# AB-AudioMatrix-6x6.net
KiCad netlist of a schematic drawn in EAGLE
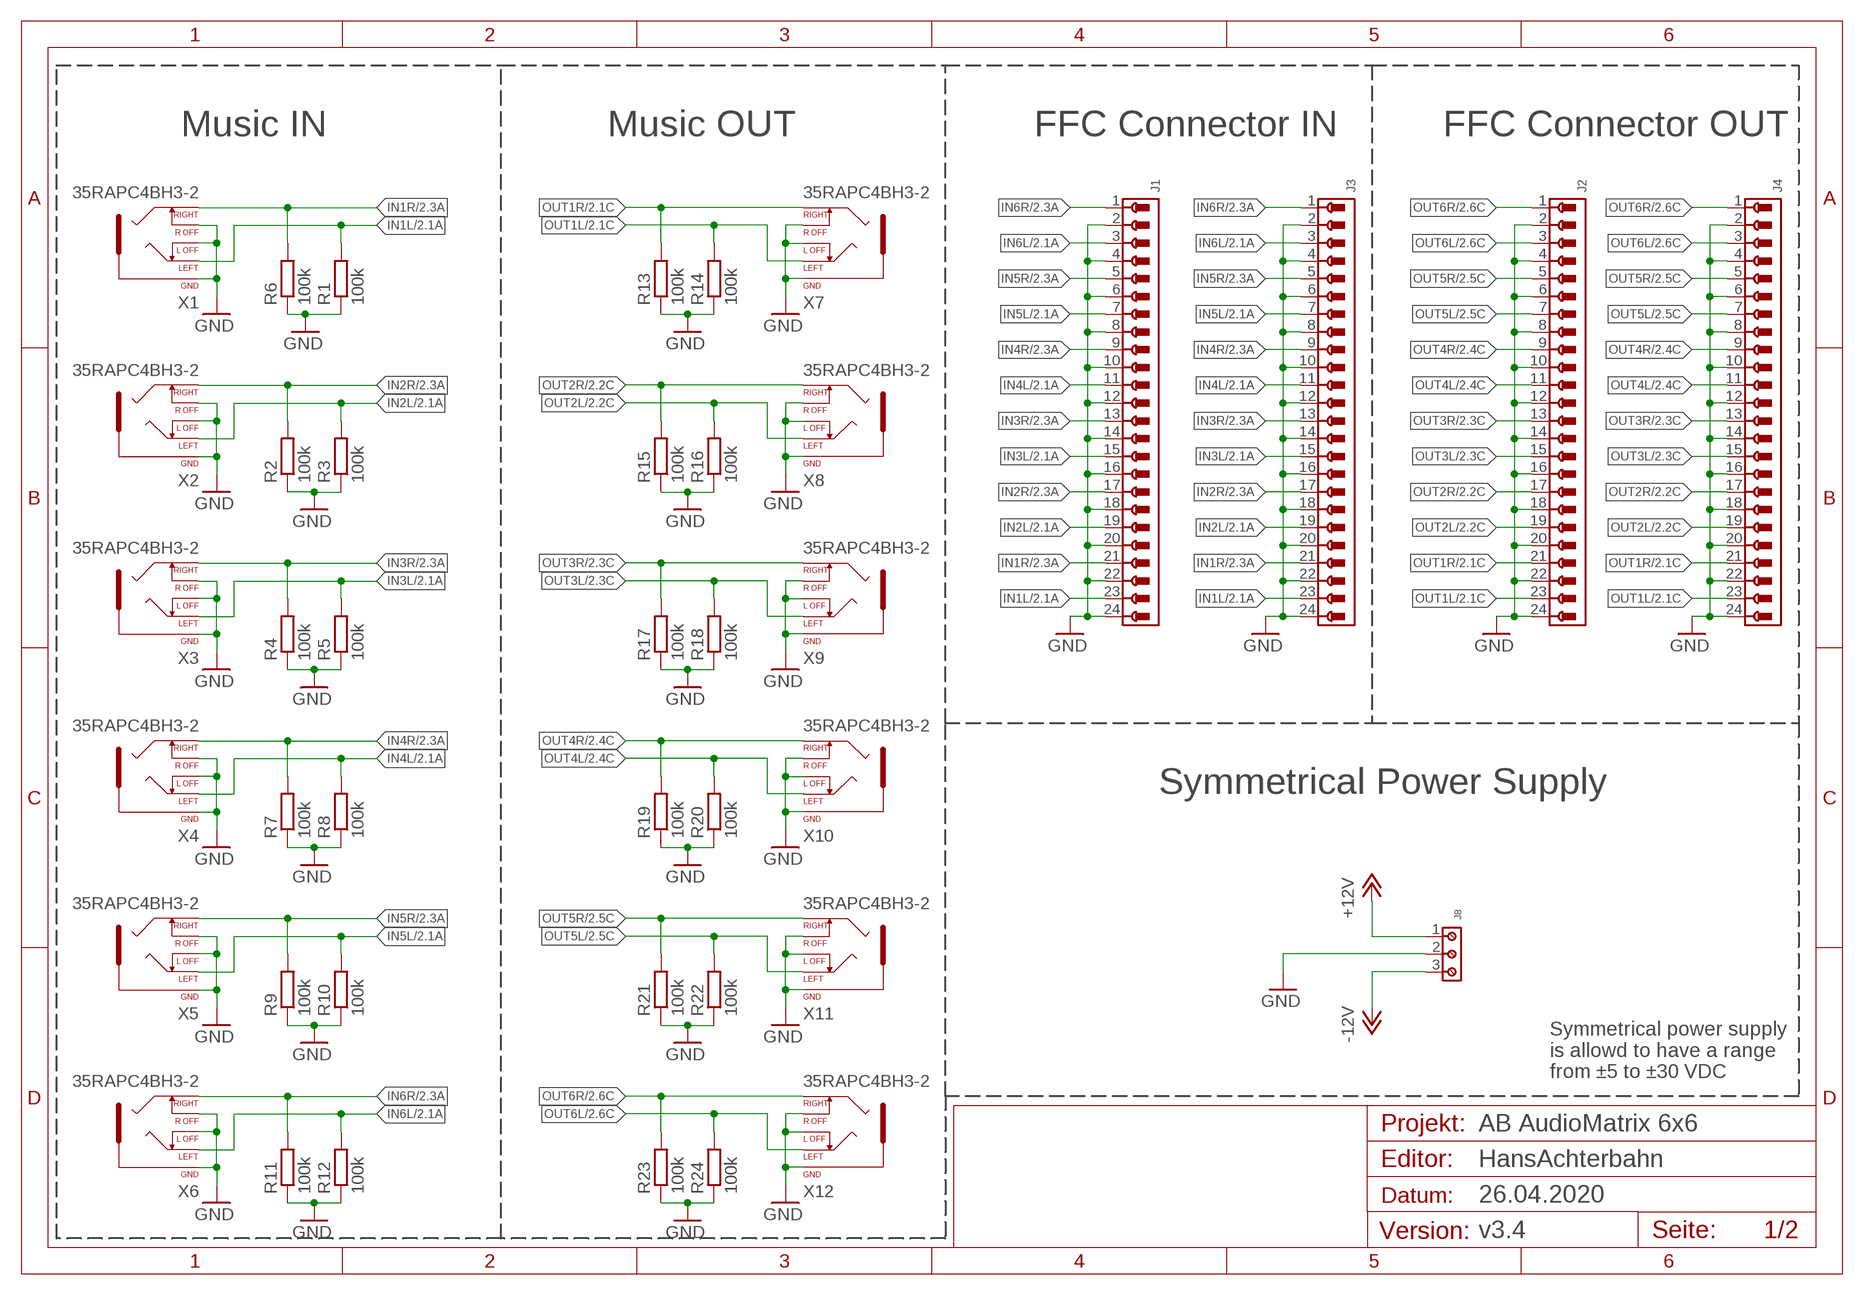
[diagram p0: schematic, sheet 1]
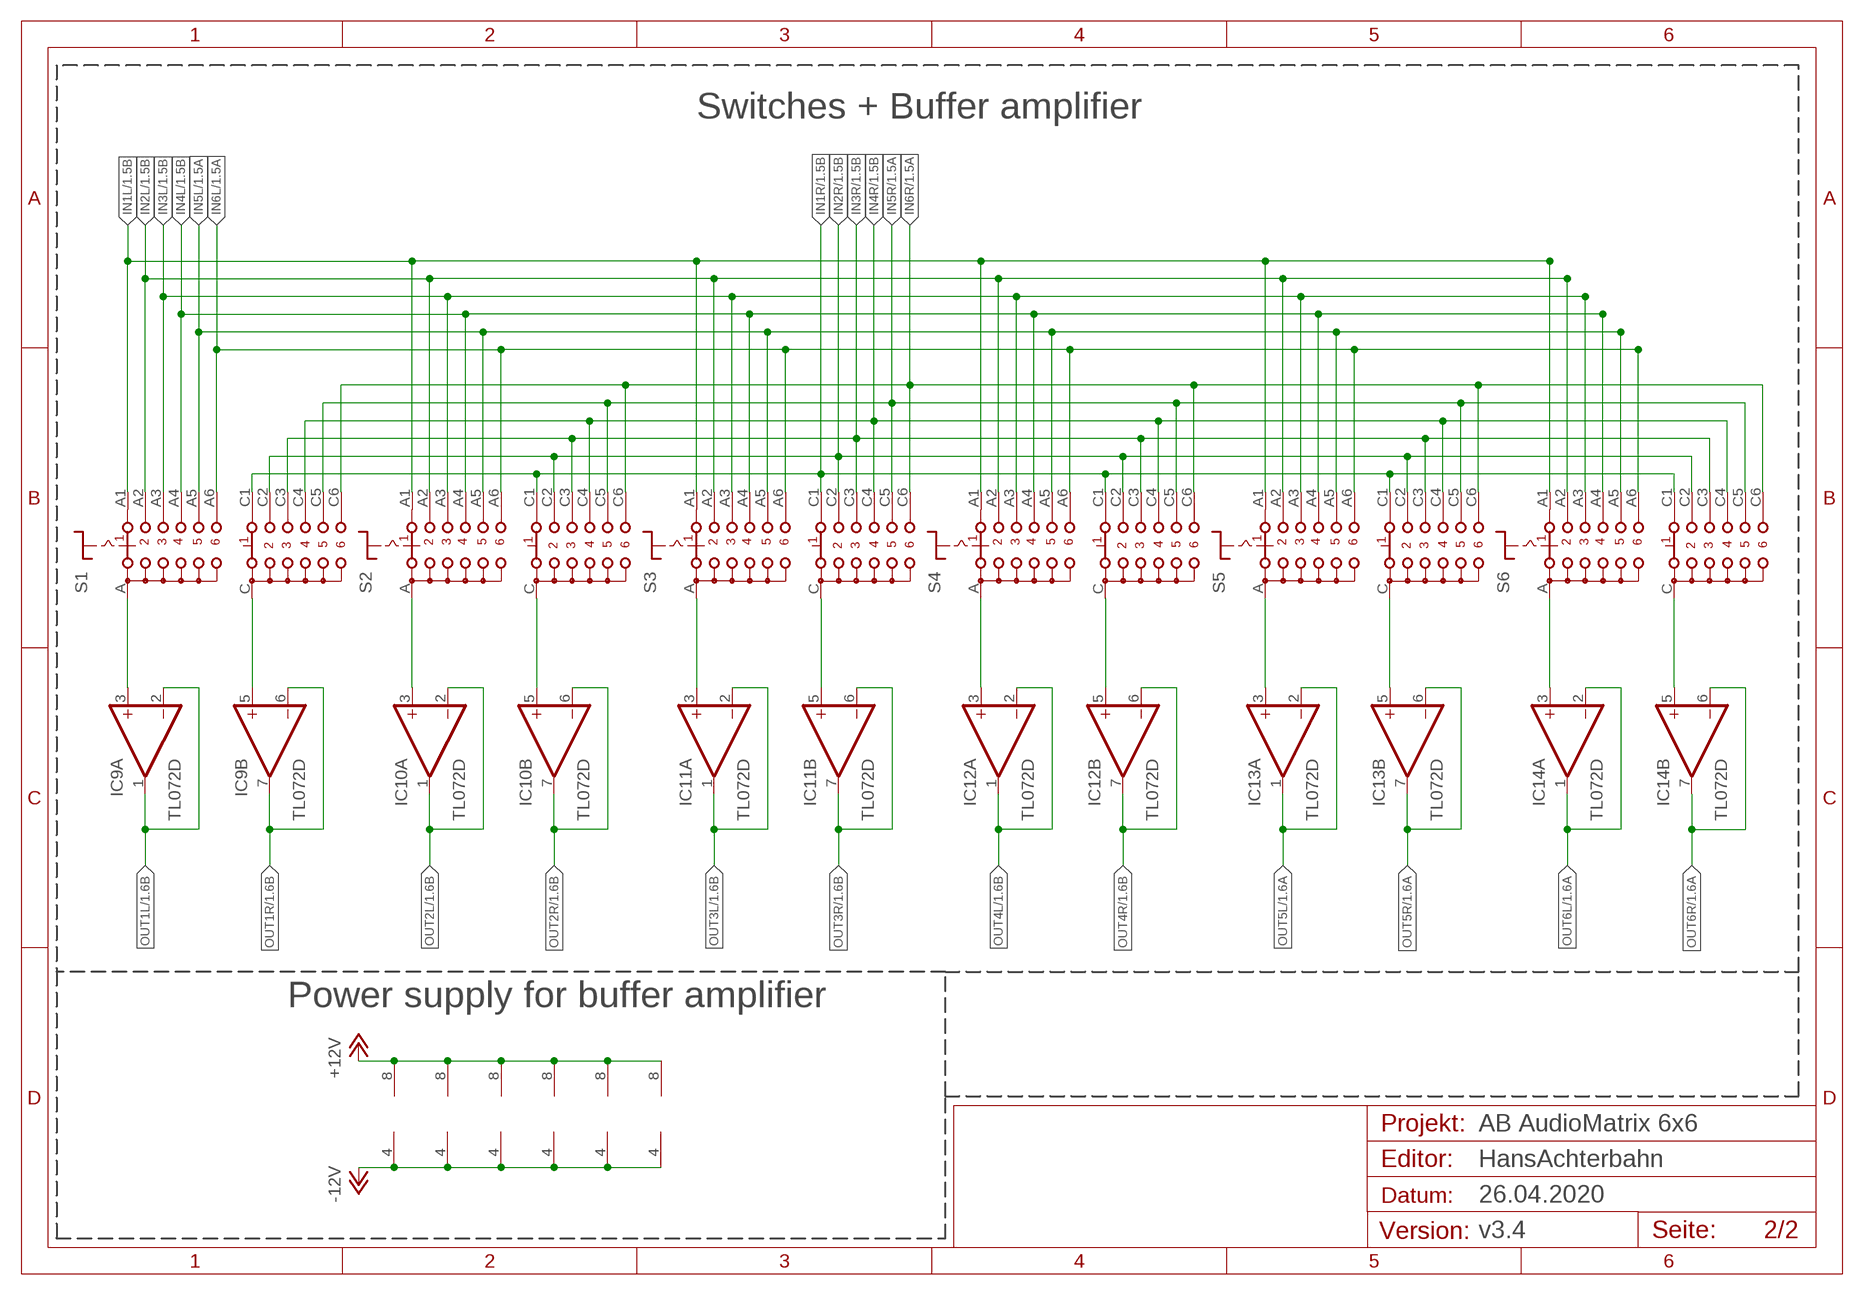
[diagram p1: schematic, sheet 2]

(export (version "E")
  (design (tool "Eeschema 10.0.6"))
  (components
    (comp (ref "J1")
      (value "6861XX188622_686124188622")
      (footprint "eagle-import:686124188622")
      (libsource (lib "eagle-import") (part "6861XX188622_686124188622"))
    )
    (comp (ref "J2")
      (value "6861XX188622_686124188622")
      (footprint "eagle-import:686124188622")
      (libsource (lib "eagle-import") (part "6861XX188622_686124188622"))
    )
    (comp (ref "J3")
      (value "6861XX188622_686124188622")
      (footprint "eagle-import:686124188622")
      (libsource (lib "eagle-import") (part "6861XX188622_686124188622"))
    )
    (comp (ref "J4")
      (value "6861XX188622_686124188622")
      (footprint "eagle-import:686124188622")
      (libsource (lib "eagle-import") (part "6861XX188622_686124188622"))
    )
    (comp (ref "J8")
      (value "691102710003")
      (footprint "eagle-import:691102710003")
      (libsource (lib "eagle-import") (part "691102710003"))
    )
    (comp (ref "R1")
      (value "100k")
      (footprint "eagle-import:R0603")
      (fields (field (name "MF") "Vishay"))
      (libsource (lib "eagle-import") (part "R-EU_R0603"))
    )
    (comp (ref "R2")
      (value "100k")
      (footprint "eagle-import:R0603")
      (fields (field (name "MF") "Vishay"))
      (libsource (lib "eagle-import") (part "R-EU_R0603"))
    )
    (comp (ref "R3")
      (value "100k")
      (footprint "eagle-import:R0603")
      (fields (field (name "MF") "Vishay"))
      (libsource (lib "eagle-import") (part "R-EU_R0603"))
    )
    (comp (ref "R4")
      (value "100k")
      (footprint "eagle-import:R0603")
      (fields (field (name "MF") "Vishay"))
      (libsource (lib "eagle-import") (part "R-EU_R0603"))
    )
    (comp (ref "R5")
      (value "100k")
      (footprint "eagle-import:R0603")
      (fields (field (name "MF") "Vishay"))
      (libsource (lib "eagle-import") (part "R-EU_R0603"))
    )
    (comp (ref "R6")
      (value "100k")
      (footprint "eagle-import:R0603")
      (fields (field (name "MF") "Vishay"))
      (libsource (lib "eagle-import") (part "R-EU_R0603"))
    )
    (comp (ref "R7")
      (value "100k")
      (footprint "eagle-import:R0603")
      (fields (field (name "MF") "Vishay"))
      (libsource (lib "eagle-import") (part "R-EU_R0603"))
    )
    (comp (ref "R8")
      (value "100k")
      (footprint "eagle-import:R0603")
      (fields (field (name "MF") "Vishay"))
      (libsource (lib "eagle-import") (part "R-EU_R0603"))
    )
    (comp (ref "R9")
      (value "100k")
      (footprint "eagle-import:R0603")
      (fields (field (name "MF") "Vishay"))
      (libsource (lib "eagle-import") (part "R-EU_R0603"))
    )
    (comp (ref "R10")
      (value "100k")
      (footprint "eagle-import:R0603")
      (fields (field (name "MF") "Vishay"))
      (libsource (lib "eagle-import") (part "R-EU_R0603"))
    )
    (comp (ref "R11")
      (value "100k")
      (footprint "eagle-import:R0603")
      (fields (field (name "MF") "Vishay"))
      (libsource (lib "eagle-import") (part "R-EU_R0603"))
    )
    (comp (ref "R12")
      (value "100k")
      (footprint "eagle-import:R0603")
      (fields (field (name "MF") "Vishay"))
      (libsource (lib "eagle-import") (part "R-EU_R0603"))
    )
    (comp (ref "R13")
      (value "100k")
      (footprint "eagle-import:R0603")
      (fields (field (name "MF") "Vishay"))
      (libsource (lib "eagle-import") (part "R-EU_R0603"))
    )
    (comp (ref "R14")
      (value "100k")
      (footprint "eagle-import:R0603")
      (fields (field (name "MF") "Vishay"))
      (libsource (lib "eagle-import") (part "R-EU_R0603"))
    )
    (comp (ref "R15")
      (value "100k")
      (footprint "eagle-import:R0603")
      (fields (field (name "MF") "Vishay"))
      (libsource (lib "eagle-import") (part "R-EU_R0603"))
    )
    (comp (ref "R16")
      (value "100k")
      (footprint "eagle-import:R0603")
      (fields (field (name "MF") "Vishay"))
      (libsource (lib "eagle-import") (part "R-EU_R0603"))
    )
    (comp (ref "R17")
      (value "100k")
      (footprint "eagle-import:R0603")
      (fields (field (name "MF") "Vishay"))
      (libsource (lib "eagle-import") (part "R-EU_R0603"))
    )
    (comp (ref "R18")
      (value "100k")
      (footprint "eagle-import:R0603")
      (fields (field (name "MF") "Vishay"))
      (libsource (lib "eagle-import") (part "R-EU_R0603"))
    )
    (comp (ref "R19")
      (value "100k")
      (footprint "eagle-import:R0603")
      (fields (field (name "MF") "Vishay"))
      (libsource (lib "eagle-import") (part "R-EU_R0603"))
    )
    (comp (ref "R20")
      (value "100k")
      (footprint "eagle-import:R0603")
      (fields (field (name "MF") "Vishay"))
      (libsource (lib "eagle-import") (part "R-EU_R0603"))
    )
    (comp (ref "R21")
      (value "100k")
      (footprint "eagle-import:R0603")
      (fields (field (name "MF") "Vishay"))
      (libsource (lib "eagle-import") (part "R-EU_R0603"))
    )
    (comp (ref "R22")
      (value "100k")
      (footprint "eagle-import:R0603")
      (fields (field (name "MF") "Vishay"))
      (libsource (lib "eagle-import") (part "R-EU_R0603"))
    )
    (comp (ref "R23")
      (value "100k")
      (footprint "eagle-import:R0603")
      (fields (field (name "MF") "Vishay"))
      (libsource (lib "eagle-import") (part "R-EU_R0603"))
    )
    (comp (ref "R24")
      (value "100k")
      (footprint "eagle-import:R0603")
      (fields (field (name "MF") "Vishay"))
      (libsource (lib "eagle-import") (part "R-EU_R0603"))
    )
    (comp (ref "X1")
      (value "35RAPC4BH3-2")
      (footprint "eagle-import:SWITCHCRAFT_35RAPC4BH3")
      (fields
        (field (name "MF") "Switchcraft")
        (field (name "MF_1") "Switchcraft")
        (field (name "MFN") "35RAPC4BH3")
        (field (name "MOUSER") "502-35RAPC4BH3")
        (field (name "RS-ONLINE") "878-7229")
      )
      (libsource (lib "eagle-import") (part "35RAPC4BH3-2"))
    )
    (comp (ref "X2")
      (value "35RAPC4BH3-2")
      (footprint "eagle-import:SWITCHCRAFT_35RAPC4BH3")
      (fields (field (name "MF") "Switchcraft"))
      (libsource (lib "eagle-import") (part "35RAPC4BH3-2"))
    )
    (comp (ref "X3")
      (value "35RAPC4BH3-2")
      (footprint "eagle-import:SWITCHCRAFT_35RAPC4BH3")
      (fields (field (name "MF") "Switchcraft"))
      (libsource (lib "eagle-import") (part "35RAPC4BH3-2"))
    )
    (comp (ref "X4")
      (value "35RAPC4BH3-2")
      (footprint "eagle-import:SWITCHCRAFT_35RAPC4BH3")
      (fields (field (name "MF") "Switchcraft"))
      (libsource (lib "eagle-import") (part "35RAPC4BH3-2"))
    )
    (comp (ref "X5")
      (value "35RAPC4BH3-2")
      (footprint "eagle-import:SWITCHCRAFT_35RAPC4BH3")
      (fields (field (name "MF") "Switchcraft"))
      (libsource (lib "eagle-import") (part "35RAPC4BH3-2"))
    )
    (comp (ref "X6")
      (value "35RAPC4BH3-2")
      (footprint "eagle-import:SWITCHCRAFT_35RAPC4BH3")
      (fields (field (name "MF") "Switchcraft"))
      (libsource (lib "eagle-import") (part "35RAPC4BH3-2"))
    )
    (comp (ref "X7")
      (value "35RAPC4BH3-2")
      (footprint "eagle-import:SWITCHCRAFT_35RAPC4BH3")
      (fields (field (name "MF") "Switchcraft"))
      (libsource (lib "eagle-import") (part "35RAPC4BH3-2"))
    )
    (comp (ref "X8")
      (value "35RAPC4BH3-2")
      (footprint "eagle-import:SWITCHCRAFT_35RAPC4BH3")
      (fields (field (name "MF") "Switchcraft"))
      (libsource (lib "eagle-import") (part "35RAPC4BH3-2"))
    )
    (comp (ref "X9")
      (value "35RAPC4BH3-2")
      (footprint "eagle-import:SWITCHCRAFT_35RAPC4BH3")
      (fields (field (name "MF") "Switchcraft"))
      (libsource (lib "eagle-import") (part "35RAPC4BH3-2"))
    )
    (comp (ref "X10")
      (value "35RAPC4BH3-2")
      (footprint "eagle-import:SWITCHCRAFT_35RAPC4BH3")
      (fields (field (name "MF") "Switchcraft"))
      (libsource (lib "eagle-import") (part "35RAPC4BH3-2"))
    )
    (comp (ref "X11")
      (value "35RAPC4BH3-2")
      (footprint "eagle-import:SWITCHCRAFT_35RAPC4BH3")
      (fields (field (name "MF") "Switchcraft"))
      (libsource (lib "eagle-import") (part "35RAPC4BH3-2"))
    )
    (comp (ref "X12")
      (value "35RAPC4BH3-2")
      (footprint "eagle-import:SWITCHCRAFT_35RAPC4BH3")
      (fields (field (name "MF") "Switchcraft"))
      (libsource (lib "eagle-import") (part "35RAPC4BH3-2"))
    )
    (comp (ref "IC9")
      (value "TL072D")
      (footprint "eagle-import:SO08")
      (libsource (lib "eagle-import") (part "TL072D"))
    )
    (comp (ref "IC10")
      (value "TL072D")
      (footprint "eagle-import:SO08")
      (libsource (lib "eagle-import") (part "TL072D"))
    )
    (comp (ref "IC11")
      (value "TL072D")
      (footprint "eagle-import:SO08")
      (libsource (lib "eagle-import") (part "TL072D"))
    )
    (comp (ref "IC12")
      (value "TL072D")
      (footprint "eagle-import:SO08")
      (libsource (lib "eagle-import") (part "TL072D"))
    )
    (comp (ref "IC13")
      (value "TL072D")
      (footprint "eagle-import:SO08")
      (libsource (lib "eagle-import") (part "TL072D"))
    )
    (comp (ref "IC14")
      (value "TL072D")
      (footprint "eagle-import:SO08")
      (libsource (lib "eagle-import") (part "TL072D"))
    )
    (comp (ref "S1")
      (value "CK102X06")
      (footprint "eagle-import:CK102X06")
      (fields (field (name "MF") "Lorlin"))
      (libsource (lib "eagle-import") (part "CK102X06"))
    )
    (comp (ref "S2")
      (value "CK102X06")
      (footprint "eagle-import:CK102X06")
      (fields (field (name "MF") "Lorlin"))
      (libsource (lib "eagle-import") (part "CK102X06"))
    )
    (comp (ref "S3")
      (value "CK102X06")
      (footprint "eagle-import:CK102X06")
      (fields (field (name "MF") "Lorlin"))
      (libsource (lib "eagle-import") (part "CK102X06"))
    )
    (comp (ref "S4")
      (value "CK102X06")
      (footprint "eagle-import:CK102X06")
      (fields (field (name "MF") "Lorlin"))
      (libsource (lib "eagle-import") (part "CK102X06"))
    )
    (comp (ref "S5")
      (value "CK102X06")
      (footprint "eagle-import:CK102X06")
      (fields (field (name "MF") "Lorlin"))
      (libsource (lib "eagle-import") (part "CK102X06"))
    )
    (comp (ref "S6")
      (value "CK102X06")
      (footprint "eagle-import:CK102X06")
      (fields (field (name "MF") "Lorlin"))
      (libsource (lib "eagle-import") (part "CK102X06"))
    )
  )
  (nets
    (net (code "1") (name "+12V") (class "Default")
      (node (ref "IC10") (pin "8") (pinfunction "V+_8") (pintype "power_in"))
      (node (ref "IC11") (pin "8") (pinfunction "V+_8") (pintype "power_in"))
      (node (ref "IC12") (pin "8") (pinfunction "V+_8") (pintype "power_in"))
      (node (ref "IC13") (pin "8") (pinfunction "V+_8") (pintype "power_in"))
      (node (ref "IC14") (pin "8") (pinfunction "V+_8") (pintype "power_in"))
      (node (ref "IC9") (pin "8") (pinfunction "V+_8") (pintype "power_in"))
      (node (ref "J8") (pin "1") (pinfunction "1_1") (pintype "passive"))
    )
    (net (code "2") (name "-12V") (class "Default")
      (node (ref "IC10") (pin "4") (pinfunction "V-_4") (pintype "power_in"))
      (node (ref "IC11") (pin "4") (pinfunction "V-_4") (pintype "power_in"))
      (node (ref "IC12") (pin "4") (pinfunction "V-_4") (pintype "power_in"))
      (node (ref "IC13") (pin "4") (pinfunction "V-_4") (pintype "power_in"))
      (node (ref "IC14") (pin "4") (pinfunction "V-_4") (pintype "power_in"))
      (node (ref "IC9") (pin "4") (pinfunction "V-_4") (pintype "power_in"))
      (node (ref "J8") (pin "3") (pinfunction "3_3") (pintype "passive"))
    )
    (net (code "3") (name "GND") (class "Default")
      (node (ref "J1") (pin "10") (pinfunction "10_10") (pintype "passive"))
      (node (ref "J1") (pin "12") (pinfunction "12_12") (pintype "passive"))
      (node (ref "J1") (pin "14") (pinfunction "14_14") (pintype "passive"))
      (node (ref "J1") (pin "16") (pinfunction "16_16") (pintype "passive"))
      (node (ref "J1") (pin "18") (pinfunction "18_18") (pintype "passive"))
      (node (ref "J1") (pin "2") (pinfunction "2_2") (pintype "passive"))
      (node (ref "J1") (pin "20") (pinfunction "20_20") (pintype "passive"))
      (node (ref "J1") (pin "22") (pinfunction "22_22") (pintype "passive"))
      (node (ref "J1") (pin "24") (pinfunction "24_24") (pintype "passive"))
      (node (ref "J1") (pin "4") (pinfunction "4_4") (pintype "passive"))
      (node (ref "J1") (pin "6") (pinfunction "6_6") (pintype "passive"))
      (node (ref "J1") (pin "8") (pinfunction "8_8") (pintype "passive"))
      (node (ref "J2") (pin "10") (pinfunction "10_10") (pintype "passive"))
      (node (ref "J2") (pin "12") (pinfunction "12_12") (pintype "passive"))
      (node (ref "J2") (pin "14") (pinfunction "14_14") (pintype "passive"))
      (node (ref "J2") (pin "16") (pinfunction "16_16") (pintype "passive"))
      (node (ref "J2") (pin "18") (pinfunction "18_18") (pintype "passive"))
      (node (ref "J2") (pin "2") (pinfunction "2_2") (pintype "passive"))
      (node (ref "J2") (pin "20") (pinfunction "20_20") (pintype "passive"))
      (node (ref "J2") (pin "22") (pinfunction "22_22") (pintype "passive"))
      (node (ref "J2") (pin "24") (pinfunction "24_24") (pintype "passive"))
      (node (ref "J2") (pin "4") (pinfunction "4_4") (pintype "passive"))
      (node (ref "J2") (pin "6") (pinfunction "6_6") (pintype "passive"))
      (node (ref "J2") (pin "8") (pinfunction "8_8") (pintype "passive"))
      (node (ref "J3") (pin "10") (pinfunction "10_10") (pintype "passive"))
      (node (ref "J3") (pin "12") (pinfunction "12_12") (pintype "passive"))
      (node (ref "J3") (pin "14") (pinfunction "14_14") (pintype "passive"))
      (node (ref "J3") (pin "16") (pinfunction "16_16") (pintype "passive"))
      (node (ref "J3") (pin "18") (pinfunction "18_18") (pintype "passive"))
      (node (ref "J3") (pin "2") (pinfunction "2_2") (pintype "passive"))
      (node (ref "J3") (pin "20") (pinfunction "20_20") (pintype "passive"))
      (node (ref "J3") (pin "22") (pinfunction "22_22") (pintype "passive"))
      (node (ref "J3") (pin "24") (pinfunction "24_24") (pintype "passive"))
      (node (ref "J3") (pin "4") (pinfunction "4_4") (pintype "passive"))
      (node (ref "J3") (pin "6") (pinfunction "6_6") (pintype "passive"))
      (node (ref "J3") (pin "8") (pinfunction "8_8") (pintype "passive"))
      (node (ref "J4") (pin "10") (pinfunction "10_10") (pintype "passive"))
      (node (ref "J4") (pin "12") (pinfunction "12_12") (pintype "passive"))
      (node (ref "J4") (pin "14") (pinfunction "14_14") (pintype "passive"))
      (node (ref "J4") (pin "16") (pinfunction "16_16") (pintype "passive"))
      (node (ref "J4") (pin "18") (pinfunction "18_18") (pintype "passive"))
      (node (ref "J4") (pin "2") (pinfunction "2_2") (pintype "passive"))
      (node (ref "J4") (pin "20") (pinfunction "20_20") (pintype "passive"))
      (node (ref "J4") (pin "22") (pinfunction "22_22") (pintype "passive"))
      (node (ref "J4") (pin "24") (pinfunction "24_24") (pintype "passive"))
      (node (ref "J4") (pin "4") (pinfunction "4_4") (pintype "passive"))
      (node (ref "J4") (pin "6") (pinfunction "6_6") (pintype "passive"))
      (node (ref "J4") (pin "8") (pinfunction "8_8") (pintype "passive"))
      (node (ref "J8") (pin "2") (pinfunction "2_2") (pintype "passive"))
      (node (ref "R1") (pin "1") (pinfunction "1_1") (pintype "passive"))
      (node (ref "R10") (pin "1") (pinfunction "1_1") (pintype "passive"))
      (node (ref "R11") (pin "1") (pinfunction "1_1") (pintype "passive"))
      (node (ref "R12") (pin "1") (pinfunction "1_1") (pintype "passive"))
      (node (ref "R13") (pin "1") (pinfunction "1_1") (pintype "passive"))
      (node (ref "R14") (pin "1") (pinfunction "1_1") (pintype "passive"))
      (node (ref "R15") (pin "1") (pinfunction "1_1") (pintype "passive"))
      (node (ref "R16") (pin "1") (pinfunction "1_1") (pintype "passive"))
      (node (ref "R17") (pin "1") (pinfunction "1_1") (pintype "passive"))
      (node (ref "R18") (pin "1") (pinfunction "1_1") (pintype "passive"))
      (node (ref "R19") (pin "1") (pinfunction "1_1") (pintype "passive"))
      (node (ref "R2") (pin "1") (pinfunction "1_1") (pintype "passive"))
      (node (ref "R20") (pin "1") (pinfunction "1_1") (pintype "passive"))
      (node (ref "R21") (pin "1") (pinfunction "1_1") (pintype "passive"))
      (node (ref "R22") (pin "1") (pinfunction "1_1") (pintype "passive"))
      (node (ref "R23") (pin "1") (pinfunction "1_1") (pintype "passive"))
      (node (ref "R24") (pin "1") (pinfunction "1_1") (pintype "passive"))
      (node (ref "R3") (pin "1") (pinfunction "1_1") (pintype "passive"))
      (node (ref "R4") (pin "1") (pinfunction "1_1") (pintype "passive"))
      (node (ref "R5") (pin "1") (pinfunction "1_1") (pintype "passive"))
      (node (ref "R6") (pin "1") (pinfunction "1_1") (pintype "passive"))
      (node (ref "R7") (pin "1") (pinfunction "1_1") (pintype "passive"))
      (node (ref "R8") (pin "1") (pinfunction "1_1") (pintype "passive"))
      (node (ref "R9") (pin "1") (pinfunction "1_1") (pintype "passive"))
      (node (ref "X1") (pin "1") (pinfunction "GND_1") (pintype "bidirectional"))
      (node (ref "X1") (pin "3") (pinfunction "RIGHT_OFF_3") (pintype "bidirectional"))
      (node (ref "X1") (pin "4") (pinfunction "LEFT_OFF_4") (pintype "bidirectional"))
      (node (ref "X10") (pin "1") (pinfunction "GND_1") (pintype "bidirectional"))
      (node (ref "X10") (pin "3") (pinfunction "RIGHT_OFF_3") (pintype "bidirectional"))
      (node (ref "X10") (pin "4") (pinfunction "LEFT_OFF_4") (pintype "bidirectional"))
      (node (ref "X11") (pin "1") (pinfunction "GND_1") (pintype "bidirectional"))
      (node (ref "X11") (pin "3") (pinfunction "RIGHT_OFF_3") (pintype "bidirectional"))
      (node (ref "X11") (pin "4") (pinfunction "LEFT_OFF_4") (pintype "bidirectional"))
      (node (ref "X12") (pin "1") (pinfunction "GND_1") (pintype "bidirectional"))
      (node (ref "X12") (pin "3") (pinfunction "RIGHT_OFF_3") (pintype "bidirectional"))
      (node (ref "X12") (pin "4") (pinfunction "LEFT_OFF_4") (pintype "bidirectional"))
      (node (ref "X2") (pin "1") (pinfunction "GND_1") (pintype "bidirectional"))
      (node (ref "X2") (pin "3") (pinfunction "RIGHT_OFF_3") (pintype "bidirectional"))
      (node (ref "X2") (pin "4") (pinfunction "LEFT_OFF_4") (pintype "bidirectional"))
      (node (ref "X3") (pin "1") (pinfunction "GND_1") (pintype "bidirectional"))
      (node (ref "X3") (pin "3") (pinfunction "RIGHT_OFF_3") (pintype "bidirectional"))
      (node (ref "X3") (pin "4") (pinfunction "LEFT_OFF_4") (pintype "bidirectional"))
      (node (ref "X4") (pin "1") (pinfunction "GND_1") (pintype "bidirectional"))
      (node (ref "X4") (pin "3") (pinfunction "RIGHT_OFF_3") (pintype "bidirectional"))
      (node (ref "X4") (pin "4") (pinfunction "LEFT_OFF_4") (pintype "bidirectional"))
      (node (ref "X5") (pin "1") (pinfunction "GND_1") (pintype "bidirectional"))
      (node (ref "X5") (pin "3") (pinfunction "RIGHT_OFF_3") (pintype "bidirectional"))
      (node (ref "X5") (pin "4") (pinfunction "LEFT_OFF_4") (pintype "bidirectional"))
      (node (ref "X6") (pin "1") (pinfunction "GND_1") (pintype "bidirectional"))
      (node (ref "X6") (pin "3") (pinfunction "RIGHT_OFF_3") (pintype "bidirectional"))
      (node (ref "X6") (pin "4") (pinfunction "LEFT_OFF_4") (pintype "bidirectional"))
      (node (ref "X7") (pin "1") (pinfunction "GND_1") (pintype "bidirectional"))
      (node (ref "X7") (pin "3") (pinfunction "RIGHT_OFF_3") (pintype "bidirectional"))
      (node (ref "X7") (pin "4") (pinfunction "LEFT_OFF_4") (pintype "bidirectional"))
      (node (ref "X8") (pin "1") (pinfunction "GND_1") (pintype "bidirectional"))
      (node (ref "X8") (pin "3") (pinfunction "RIGHT_OFF_3") (pintype "bidirectional"))
      (node (ref "X8") (pin "4") (pinfunction "LEFT_OFF_4") (pintype "bidirectional"))
      (node (ref "X9") (pin "1") (pinfunction "GND_1") (pintype "bidirectional"))
      (node (ref "X9") (pin "3") (pinfunction "RIGHT_OFF_3") (pintype "bidirectional"))
      (node (ref "X9") (pin "4") (pinfunction "LEFT_OFF_4") (pintype "bidirectional"))
    )
    (net (code "4") (name "IN1L") (class "Default")
      (node (ref "J1") (pin "23") (pinfunction "23_23") (pintype "passive"))
      (node (ref "J3") (pin "23") (pinfunction "23_23") (pintype "passive"))
      (node (ref "R1") (pin "2") (pinfunction "2_2") (pintype "passive"))
      (node (ref "S1") (pin "A1") (pinfunction "A1_A1") (pintype "passive"))
      (node (ref "S2") (pin "A1") (pinfunction "A1_A1") (pintype "passive"))
      (node (ref "S3") (pin "A1") (pinfunction "A1_A1") (pintype "passive"))
      (node (ref "S4") (pin "A1") (pinfunction "A1_A1") (pintype "passive"))
      (node (ref "S5") (pin "A1") (pinfunction "A1_A1") (pintype "passive"))
      (node (ref "S6") (pin "A1") (pinfunction "A1_A1") (pintype "passive"))
      (node (ref "X1") (pin "5") (pinfunction "LEFT_5") (pintype "bidirectional"))
    )
    (net (code "5") (name "IN1R") (class "Default")
      (node (ref "J1") (pin "21") (pinfunction "21_21") (pintype "passive"))
      (node (ref "J3") (pin "21") (pinfunction "21_21") (pintype "passive"))
      (node (ref "R6") (pin "2") (pinfunction "2_2") (pintype "passive"))
      (node (ref "S1") (pin "C1") (pinfunction "C1_C1") (pintype "passive"))
      (node (ref "S2") (pin "C1") (pinfunction "C1_C1") (pintype "passive"))
      (node (ref "S3") (pin "C1") (pinfunction "C1_C1") (pintype "passive"))
      (node (ref "S4") (pin "C1") (pinfunction "C1_C1") (pintype "passive"))
      (node (ref "S5") (pin "C1") (pinfunction "C1_C1") (pintype "passive"))
      (node (ref "S6") (pin "C1") (pinfunction "C1_C1") (pintype "passive"))
      (node (ref "X1") (pin "2") (pinfunction "RIGHT_2") (pintype "bidirectional"))
    )
    (net (code "6") (name "IN2L") (class "Default")
      (node (ref "J1") (pin "19") (pinfunction "19_19") (pintype "passive"))
      (node (ref "J3") (pin "19") (pinfunction "19_19") (pintype "passive"))
      (node (ref "R3") (pin "2") (pinfunction "2_2") (pintype "passive"))
      (node (ref "S1") (pin "A2") (pinfunction "A2_A2") (pintype "passive"))
      (node (ref "S2") (pin "A2") (pinfunction "A2_A2") (pintype "passive"))
      (node (ref "S3") (pin "A2") (pinfunction "A2_A2") (pintype "passive"))
      (node (ref "S4") (pin "A2") (pinfunction "A2_A2") (pintype "passive"))
      (node (ref "S5") (pin "A2") (pinfunction "A2_A2") (pintype "passive"))
      (node (ref "S6") (pin "A2") (pinfunction "A2_A2") (pintype "passive"))
      (node (ref "X2") (pin "5") (pinfunction "LEFT_5") (pintype "bidirectional"))
    )
    (net (code "7") (name "IN2R") (class "Default")
      (node (ref "J1") (pin "17") (pinfunction "17_17") (pintype "passive"))
      (node (ref "J3") (pin "17") (pinfunction "17_17") (pintype "passive"))
      (node (ref "R2") (pin "2") (pinfunction "2_2") (pintype "passive"))
      (node (ref "S1") (pin "C2") (pinfunction "C2_C2") (pintype "passive"))
      (node (ref "S2") (pin "C2") (pinfunction "C2_C2") (pintype "passive"))
      (node (ref "S3") (pin "C2") (pinfunction "C2_C2") (pintype "passive"))
      (node (ref "S4") (pin "C2") (pinfunction "C2_C2") (pintype "passive"))
      (node (ref "S5") (pin "C2") (pinfunction "C2_C2") (pintype "passive"))
      (node (ref "S6") (pin "C2") (pinfunction "C2_C2") (pintype "passive"))
      (node (ref "X2") (pin "2") (pinfunction "RIGHT_2") (pintype "bidirectional"))
    )
    (net (code "8") (name "IN3L") (class "Default")
      (node (ref "J1") (pin "15") (pinfunction "15_15") (pintype "passive"))
      (node (ref "J3") (pin "15") (pinfunction "15_15") (pintype "passive"))
      (node (ref "R5") (pin "2") (pinfunction "2_2") (pintype "passive"))
      (node (ref "S1") (pin "A3") (pinfunction "A3_A3") (pintype "passive"))
      (node (ref "S2") (pin "A3") (pinfunction "A3_A3") (pintype "passive"))
      (node (ref "S3") (pin "A3") (pinfunction "A3_A3") (pintype "passive"))
      (node (ref "S4") (pin "A3") (pinfunction "A3_A3") (pintype "passive"))
      (node (ref "S5") (pin "A3") (pinfunction "A3_A3") (pintype "passive"))
      (node (ref "S6") (pin "A3") (pinfunction "A3_A3") (pintype "passive"))
      (node (ref "X3") (pin "5") (pinfunction "LEFT_5") (pintype "bidirectional"))
    )
    (net (code "9") (name "IN3R") (class "Default")
      (node (ref "J1") (pin "13") (pinfunction "13_13") (pintype "passive"))
      (node (ref "J3") (pin "13") (pinfunction "13_13") (pintype "passive"))
      (node (ref "R4") (pin "2") (pinfunction "2_2") (pintype "passive"))
      (node (ref "S1") (pin "C3") (pinfunction "C3_C3") (pintype "passive"))
      (node (ref "S2") (pin "C3") (pinfunction "C3_C3") (pintype "passive"))
      (node (ref "S3") (pin "C3") (pinfunction "C3_C3") (pintype "passive"))
      (node (ref "S4") (pin "C3") (pinfunction "C3_C3") (pintype "passive"))
      (node (ref "S5") (pin "C3") (pinfunction "C3_C3") (pintype "passive"))
      (node (ref "S6") (pin "C3") (pinfunction "C3_C3") (pintype "passive"))
      (node (ref "X3") (pin "2") (pinfunction "RIGHT_2") (pintype "bidirectional"))
    )
    (net (code "10") (name "IN4L") (class "Default")
      (node (ref "J1") (pin "11") (pinfunction "11_11") (pintype "passive"))
      (node (ref "J3") (pin "11") (pinfunction "11_11") (pintype "passive"))
      (node (ref "R8") (pin "2") (pinfunction "2_2") (pintype "passive"))
      (node (ref "S1") (pin "A4") (pinfunction "A4_A4") (pintype "passive"))
      (node (ref "S2") (pin "A4") (pinfunction "A4_A4") (pintype "passive"))
      (node (ref "S3") (pin "A4") (pinfunction "A4_A4") (pintype "passive"))
      (node (ref "S4") (pin "A4") (pinfunction "A4_A4") (pintype "passive"))
      (node (ref "S5") (pin "A4") (pinfunction "A4_A4") (pintype "passive"))
      (node (ref "S6") (pin "A4") (pinfunction "A4_A4") (pintype "passive"))
      (node (ref "X4") (pin "5") (pinfunction "LEFT_5") (pintype "bidirectional"))
    )
    (net (code "11") (name "IN4R") (class "Default")
      (node (ref "J1") (pin "9") (pinfunction "9_9") (pintype "passive"))
      (node (ref "J3") (pin "9") (pinfunction "9_9") (pintype "passive"))
      (node (ref "R7") (pin "2") (pinfunction "2_2") (pintype "passive"))
      (node (ref "S1") (pin "C4") (pinfunction "C4_C4") (pintype "passive"))
      (node (ref "S2") (pin "C4") (pinfunction "C4_C4") (pintype "passive"))
      (node (ref "S3") (pin "C4") (pinfunction "C4_C4") (pintype "passive"))
      (node (ref "S4") (pin "C4") (pinfunction "C4_C4") (pintype "passive"))
      (node (ref "S5") (pin "C4") (pinfunction "C4_C4") (pintype "passive"))
      (node (ref "S6") (pin "C4") (pinfunction "C4_C4") (pintype "passive"))
      (node (ref "X4") (pin "2") (pinfunction "RIGHT_2") (pintype "bidirectional"))
    )
    (net (code "12") (name "IN5L") (class "Default")
      (node (ref "J1") (pin "7") (pinfunction "7_7") (pintype "passive"))
      (node (ref "J3") (pin "7") (pinfunction "7_7") (pintype "passive"))
      (node (ref "R10") (pin "2") (pinfunction "2_2") (pintype "passive"))
      (node (ref "S1") (pin "A5") (pinfunction "A5_A5") (pintype "passive"))
      (node (ref "S2") (pin "A5") (pinfunction "A5_A5") (pintype "passive"))
      (node (ref "S3") (pin "A5") (pinfunction "A5_A5") (pintype "passive"))
      (node (ref "S4") (pin "A5") (pinfunction "A5_A5") (pintype "passive"))
      (node (ref "S5") (pin "A5") (pinfunction "A5_A5") (pintype "passive"))
      (node (ref "S6") (pin "A5") (pinfunction "A5_A5") (pintype "passive"))
      (node (ref "X5") (pin "5") (pinfunction "LEFT_5") (pintype "bidirectional"))
    )
    (net (code "13") (name "IN5R") (class "Default")
      (node (ref "J1") (pin "5") (pinfunction "5_5") (pintype "passive"))
      (node (ref "J3") (pin "5") (pinfunction "5_5") (pintype "passive"))
      (node (ref "R9") (pin "2") (pinfunction "2_2") (pintype "passive"))
      (node (ref "S1") (pin "C5") (pinfunction "C5_C5") (pintype "passive"))
      (node (ref "S2") (pin "C5") (pinfunction "C5_C5") (pintype "passive"))
      (node (ref "S3") (pin "C5") (pinfunction "C5_C5") (pintype "passive"))
      (node (ref "S4") (pin "C5") (pinfunction "C5_C5") (pintype "passive"))
      (node (ref "S5") (pin "C5") (pinfunction "C5_C5") (pintype "passive"))
      (node (ref "S6") (pin "C5") (pinfunction "C5_C5") (pintype "passive"))
      (node (ref "X5") (pin "2") (pinfunction "RIGHT_2") (pintype "bidirectional"))
    )
    (net (code "14") (name "IN6L") (class "Default")
      (node (ref "J1") (pin "3") (pinfunction "3_3") (pintype "passive"))
      (node (ref "J3") (pin "3") (pinfunction "3_3") (pintype "passive"))
      (node (ref "R12") (pin "2") (pinfunction "2_2") (pintype "passive"))
      (node (ref "S1") (pin "A6") (pinfunction "A6_A6") (pintype "passive"))
      (node (ref "S2") (pin "A6") (pinfunction "A6_A6") (pintype "passive"))
      (node (ref "S3") (pin "A6") (pinfunction "A6_A6") (pintype "passive"))
      (node (ref "S4") (pin "A6") (pinfunction "A6_A6") (pintype "passive"))
      (node (ref "S5") (pin "A6") (pinfunction "A6_A6") (pintype "passive"))
      (node (ref "S6") (pin "A6") (pinfunction "A6_A6") (pintype "passive"))
      (node (ref "X6") (pin "5") (pinfunction "LEFT_5") (pintype "bidirectional"))
    )
    (net (code "15") (name "IN6R") (class "Default")
      (node (ref "J1") (pin "1") (pinfunction "1_1") (pintype "passive"))
      (node (ref "J3") (pin "1") (pinfunction "1_1") (pintype "passive"))
      (node (ref "R11") (pin "2") (pinfunction "2_2") (pintype "passive"))
      (node (ref "S1") (pin "C6") (pinfunction "C6_C6") (pintype "passive"))
      (node (ref "S2") (pin "C6") (pinfunction "C6_C6") (pintype "passive"))
      (node (ref "S3") (pin "C6") (pinfunction "C6_C6") (pintype "passive"))
      (node (ref "S4") (pin "C6") (pinfunction "C6_C6") (pintype "passive"))
      (node (ref "S5") (pin "C6") (pinfunction "C6_C6") (pintype "passive"))
      (node (ref "S6") (pin "C6") (pinfunction "C6_C6") (pintype "passive"))
      (node (ref "X6") (pin "2") (pinfunction "RIGHT_2") (pintype "bidirectional"))
    )
    (net (code "16") (name "Net-(IC9A-+IN)") (class "Default")
      (node (ref "IC9") (pin "3") (pinfunction "+IN_3") (pintype "input"))
      (node (ref "S1") (pin "A") (pinfunction "A_A") (pintype "passive"))
    )
    (net (code "17") (name "Net-(IC9B-+IN)") (class "Default")
      (node (ref "IC9") (pin "5") (pinfunction "+IN_5") (pintype "input"))
      (node (ref "S1") (pin "C") (pinfunction "C_C") (pintype "passive"))
    )
    (net (code "18") (name "Net-(IC10A-+IN)") (class "Default")
      (node (ref "IC10") (pin "3") (pinfunction "+IN_3") (pintype "input"))
      (node (ref "S2") (pin "A") (pinfunction "A_A") (pintype "passive"))
    )
    (net (code "19") (name "Net-(IC10B-+IN)") (class "Default")
      (node (ref "IC10") (pin "5") (pinfunction "+IN_5") (pintype "input"))
      (node (ref "S2") (pin "C") (pinfunction "C_C") (pintype "passive"))
    )
    (net (code "20") (name "Net-(IC11A-+IN)") (class "Default")
      (node (ref "IC11") (pin "3") (pinfunction "+IN_3") (pintype "input"))
      (node (ref "S3") (pin "A") (pinfunction "A_A") (pintype "passive"))
    )
    (net (code "21") (name "Net-(IC11B-+IN)") (class "Default")
      (node (ref "IC11") (pin "5") (pinfunction "+IN_5") (pintype "input"))
      (node (ref "S3") (pin "C") (pinfunction "C_C") (pintype "passive"))
    )
    (net (code "22") (name "Net-(IC12A-+IN)") (class "Default")
      (node (ref "IC12") (pin "3") (pinfunction "+IN_3") (pintype "input"))
      (node (ref "S4") (pin "A") (pinfunction "A_A") (pintype "passive"))
    )
    (net (code "23") (name "Net-(IC12B-+IN)") (class "Default")
      (node (ref "IC12") (pin "5") (pinfunction "+IN_5") (pintype "input"))
      (node (ref "S4") (pin "C") (pinfunction "C_C") (pintype "passive"))
    )
    (net (code "24") (name "Net-(IC13A-+IN)") (class "Default")
      (node (ref "IC13") (pin "3") (pinfunction "+IN_3") (pintype "input"))
      (node (ref "S5") (pin "A") (pinfunction "A_A") (pintype "passive"))
    )
    (net (code "25") (name "Net-(IC13B-+IN)") (class "Default")
      (node (ref "IC13") (pin "5") (pinfunction "+IN_5") (pintype "input"))
      (node (ref "S5") (pin "C") (pinfunction "C_C") (pintype "passive"))
    )
    (net (code "26") (name "Net-(IC14A-+IN)") (class "Default")
      (node (ref "IC14") (pin "3") (pinfunction "+IN_3") (pintype "input"))
      (node (ref "S6") (pin "A") (pinfunction "A_A") (pintype "passive"))
    )
    (net (code "27") (name "Net-(IC14B-+IN)") (class "Default")
      (node (ref "IC14") (pin "5") (pinfunction "+IN_5") (pintype "input"))
      (node (ref "S6") (pin "C") (pinfunction "C_C") (pintype "passive"))
    )
    (net (code "28") (name "OUT1L") (class "Default")
      (node (ref "IC9") (pin "1") (pinfunction "OUT_1") (pintype "output"))
      (node (ref "IC9") (pin "2") (pinfunction "-IN_2") (pintype "input"))
      (node (ref "J2") (pin "23") (pinfunction "23_23") (pintype "passive"))
      (node (ref "J4") (pin "23") (pinfunction "23_23") (pintype "passive"))
      (node (ref "R14") (pin "2") (pinfunction "2_2") (pintype "passive"))
      (node (ref "X7") (pin "5") (pinfunction "LEFT_5") (pintype "bidirectional"))
    )
    (net (code "29") (name "OUT1R") (class "Default")
      (node (ref "IC9") (pin "6") (pinfunction "-IN_6") (pintype "input"))
      (node (ref "IC9") (pin "7") (pinfunction "OUT_7") (pintype "output"))
      (node (ref "J2") (pin "21") (pinfunction "21_21") (pintype "passive"))
      (node (ref "J4") (pin "21") (pinfunction "21_21") (pintype "passive"))
      (node (ref "R13") (pin "2") (pinfunction "2_2") (pintype "passive"))
      (node (ref "X7") (pin "2") (pinfunction "RIGHT_2") (pintype "bidirectional"))
    )
    (net (code "30") (name "OUT2L") (class "Default")
      (node (ref "IC10") (pin "1") (pinfunction "OUT_1") (pintype "output"))
      (node (ref "IC10") (pin "2") (pinfunction "-IN_2") (pintype "input"))
      (node (ref "J2") (pin "19") (pinfunction "19_19") (pintype "passive"))
      (node (ref "J4") (pin "19") (pinfunction "19_19") (pintype "passive"))
      (node (ref "R16") (pin "2") (pinfunction "2_2") (pintype "passive"))
      (node (ref "X8") (pin "5") (pinfunction "LEFT_5") (pintype "bidirectional"))
    )
    (net (code "31") (name "OUT2R") (class "Default")
      (node (ref "IC10") (pin "6") (pinfunction "-IN_6") (pintype "input"))
      (node (ref "IC10") (pin "7") (pinfunction "OUT_7") (pintype "output"))
      (node (ref "J2") (pin "17") (pinfunction "17_17") (pintype "passive"))
      (node (ref "J4") (pin "17") (pinfunction "17_17") (pintype "passive"))
      (node (ref "R15") (pin "2") (pinfunction "2_2") (pintype "passive"))
      (node (ref "X8") (pin "2") (pinfunction "RIGHT_2") (pintype "bidirectional"))
    )
    (net (code "32") (name "OUT3L") (class "Default")
      (node (ref "IC11") (pin "1") (pinfunction "OUT_1") (pintype "output"))
      (node (ref "IC11") (pin "2") (pinfunction "-IN_2") (pintype "input"))
      (node (ref "J2") (pin "15") (pinfunction "15_15") (pintype "passive"))
      (node (ref "J4") (pin "15") (pinfunction "15_15") (pintype "passive"))
      (node (ref "R18") (pin "2") (pinfunction "2_2") (pintype "passive"))
      (node (ref "X9") (pin "5") (pinfunction "LEFT_5") (pintype "bidirectional"))
    )
    (net (code "33") (name "OUT3R") (class "Default")
      (node (ref "IC11") (pin "6") (pinfunction "-IN_6") (pintype "input"))
      (node (ref "IC11") (pin "7") (pinfunction "OUT_7") (pintype "output"))
      (node (ref "J2") (pin "13") (pinfunction "13_13") (pintype "passive"))
      (node (ref "J4") (pin "13") (pinfunction "13_13") (pintype "passive"))
      (node (ref "R17") (pin "2") (pinfunction "2_2") (pintype "passive"))
      (node (ref "X9") (pin "2") (pinfunction "RIGHT_2") (pintype "bidirectional"))
    )
    (net (code "34") (name "OUT4L") (class "Default")
      (node (ref "IC12") (pin "1") (pinfunction "OUT_1") (pintype "output"))
      (node (ref "IC12") (pin "2") (pinfunction "-IN_2") (pintype "input"))
      (node (ref "J2") (pin "11") (pinfunction "11_11") (pintype "passive"))
      (node (ref "J4") (pin "11") (pinfunction "11_11") (pintype "passive"))
      (node (ref "R20") (pin "2") (pinfunction "2_2") (pintype "passive"))
      (node (ref "X10") (pin "5") (pinfunction "LEFT_5") (pintype "bidirectional"))
    )
    (net (code "35") (name "OUT4R") (class "Default")
      (node (ref "IC12") (pin "6") (pinfunction "-IN_6") (pintype "input"))
      (node (ref "IC12") (pin "7") (pinfunction "OUT_7") (pintype "output"))
      (node (ref "J2") (pin "9") (pinfunction "9_9") (pintype "passive"))
      (node (ref "J4") (pin "9") (pinfunction "9_9") (pintype "passive"))
      (node (ref "R19") (pin "2") (pinfunction "2_2") (pintype "passive"))
      (node (ref "X10") (pin "2") (pinfunction "RIGHT_2") (pintype "bidirectional"))
    )
    (net (code "36") (name "OUT5L") (class "Default")
      (node (ref "IC13") (pin "1") (pinfunction "OUT_1") (pintype "output"))
      (node (ref "IC13") (pin "2") (pinfunction "-IN_2") (pintype "input"))
      (node (ref "J2") (pin "7") (pinfunction "7_7") (pintype "passive"))
      (node (ref "J4") (pin "7") (pinfunction "7_7") (pintype "passive"))
      (node (ref "R22") (pin "2") (pinfunction "2_2") (pintype "passive"))
      (node (ref "X11") (pin "5") (pinfunction "LEFT_5") (pintype "bidirectional"))
    )
    (net (code "37") (name "OUT5R") (class "Default")
      (node (ref "IC13") (pin "6") (pinfunction "-IN_6") (pintype "input"))
      (node (ref "IC13") (pin "7") (pinfunction "OUT_7") (pintype "output"))
      (node (ref "J2") (pin "5") (pinfunction "5_5") (pintype "passive"))
      (node (ref "J4") (pin "5") (pinfunction "5_5") (pintype "passive"))
      (node (ref "R21") (pin "2") (pinfunction "2_2") (pintype "passive"))
      (node (ref "X11") (pin "2") (pinfunction "RIGHT_2") (pintype "bidirectional"))
    )
    (net (code "38") (name "OUT6L") (class "Default")
      (node (ref "IC14") (pin "1") (pinfunction "OUT_1") (pintype "output"))
      (node (ref "IC14") (pin "2") (pinfunction "-IN_2") (pintype "input"))
      (node (ref "J2") (pin "3") (pinfunction "3_3") (pintype "passive"))
      (node (ref "J4") (pin "3") (pinfunction "3_3") (pintype "passive"))
      (node (ref "R24") (pin "2") (pinfunction "2_2") (pintype "passive"))
      (node (ref "X12") (pin "5") (pinfunction "LEFT_5") (pintype "bidirectional"))
    )
    (net (code "39") (name "OUT6R") (class "Default")
      (node (ref "IC14") (pin "6") (pinfunction "-IN_6") (pintype "input"))
      (node (ref "IC14") (pin "7") (pinfunction "OUT_7") (pintype "output"))
      (node (ref "J2") (pin "1") (pinfunction "1_1") (pintype "passive"))
      (node (ref "J4") (pin "1") (pinfunction "1_1") (pintype "passive"))
      (node (ref "R23") (pin "2") (pinfunction "2_2") (pintype "passive"))
      (node (ref "X12") (pin "2") (pinfunction "RIGHT_2") (pintype "bidirectional"))
    )
  )
)
